# sbcs.net
KiCad netlist of a schematic drawn in Altium Designer
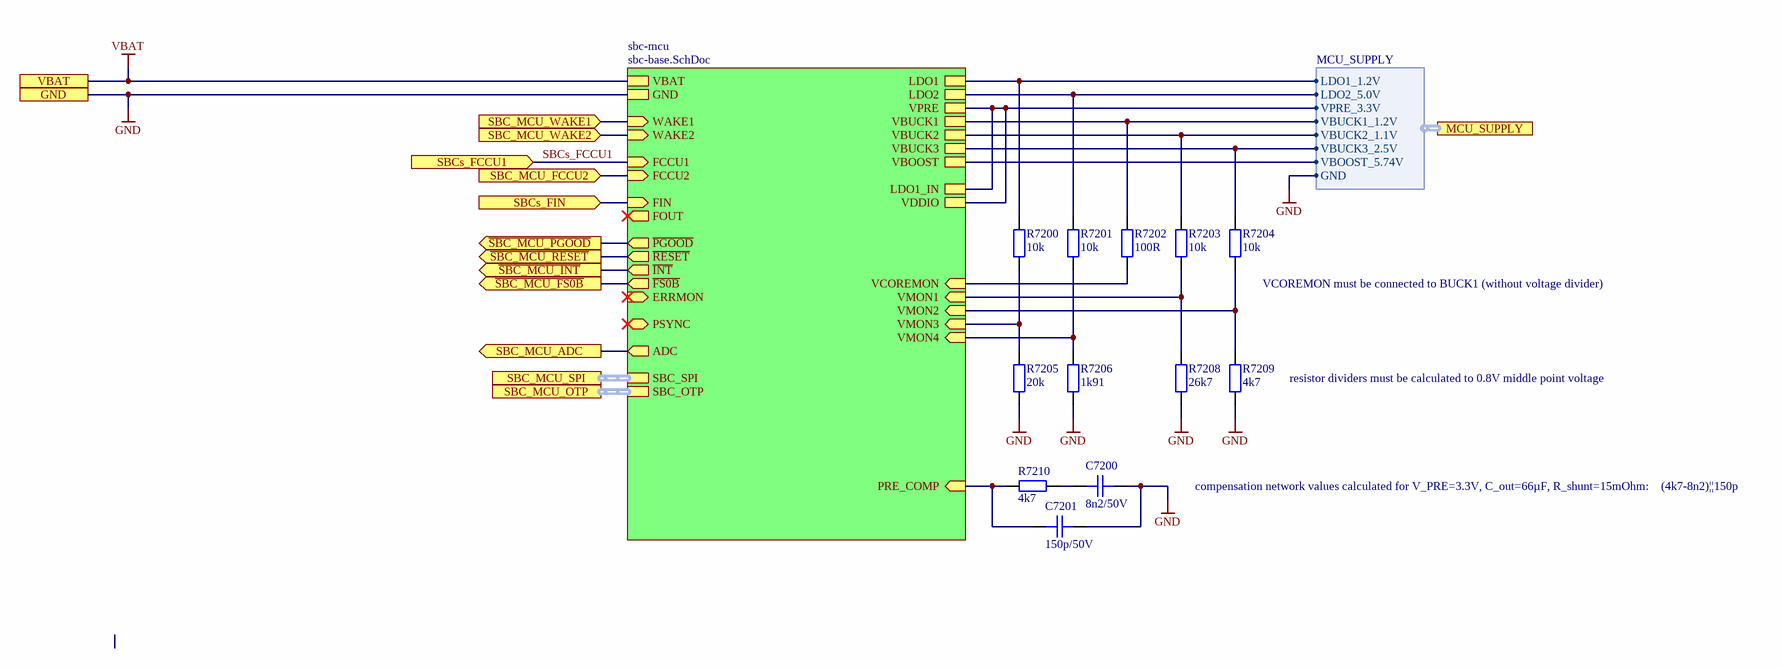
[diagram p0: sbcs.SchDoc]

(export (version "E")
  (design (tool "Eeschema 10.0.6"))
  (components
    (comp (ref "C7200")
      (value "8n2/50V")
      (footprint "CAPC1608X08N")
      (description "MLCC")
      (fields (field (name "PART NUMBER") "gen_C_ceramic_8n2_50V_C0G_0603"))
      (libsource (lib "OE750") (part "C"))
    )
    (comp (ref "C7201")
      (value "150p/50V")
      (footprint "CAPC1005X06N")
      (description "MLCC")
      (fields (field (name "PART NUMBER") "gen_C_ceramic_150p_50V_C0G_0402"))
      (libsource (lib "OE750") (part "C"))
    )
    (comp (ref "R7200")
      (value "10k")
      (footprint "RESC1005X04N")
      (description "SMD Resistor 10k 0402")
      (fields (field (name "PART NUMBER") "gen_R_10k_0402") (field (name "TOLERANCE") "1%"))
      (libsource (lib "OE750") (part "R"))
    )
    (comp (ref "R7201")
      (value "10k")
      (footprint "RESC1005X04N")
      (description "SMD Resistor 10k 0402")
      (fields (field (name "PART NUMBER") "gen_R_10k_0402") (field (name "TOLERANCE") "1%"))
      (libsource (lib "OE750") (part "R"))
    )
    (comp (ref "R7202")
      (value "100R")
      (footprint "RESC1005X04N")
      (description "SMD Resistor 100R 0402")
      (fields (field (name "PART NUMBER") "gen_R_100R_0402") (field (name "TOLERANCE") "1%"))
      (libsource (lib "OE750") (part "R"))
    )
    (comp (ref "R7203")
      (value "10k")
      (footprint "RESC1005X04N")
      (description "SMD Resistor 10k 0402")
      (fields (field (name "PART NUMBER") "gen_R_10k_0402") (field (name "TOLERANCE") "1%"))
      (libsource (lib "OE750") (part "R"))
    )
    (comp (ref "R7204")
      (value "10k")
      (footprint "RESC1005X04N")
      (description "SMD Resistor 10k 0402")
      (fields (field (name "PART NUMBER") "gen_R_10k_0402") (field (name "TOLERANCE") "1%"))
      (libsource (lib "OE750") (part "R"))
    )
    (comp (ref "R7205")
      (value "20k")
      (footprint "RESC1005X04N")
      (description "SMD Resistor 20k 0402")
      (fields (field (name "PART NUMBER") "gen_R_20k_0402") (field (name "TOLERANCE") "1%"))
      (libsource (lib "OE750") (part "R"))
    )
    (comp (ref "R7206")
      (value "1k91")
      (footprint "RESC1005X04N")
      (description "SMD Resistor 1k91 0402")
      (fields (field (name "PART NUMBER") "gen_R_1k91_0402") (field (name "TOLERANCE") "1%"))
      (libsource (lib "OE750") (part "R"))
    )
    (comp (ref "R7208")
      (value "26k7")
      (footprint "RESC1005X04N")
      (description "SMD Resistor 26k7 0402")
      (fields (field (name "PART NUMBER") "gen_R_26k7_0402") (field (name "TOLERANCE") "1%"))
      (libsource (lib "OE750") (part "R"))
    )
    (comp (ref "R7209")
      (value "4k7")
      (footprint "RESC1005X04N")
      (description "SMD Resistor 4k7 0402")
      (fields (field (name "PART NUMBER") "gen_R_4k7_0402") (field (name "TOLERANCE") "1%"))
      (libsource (lib "OE750") (part "R"))
    )
    (comp (ref "R7210")
      (value "4k7")
      (footprint "RESC1005X04N")
      (description "SMD Resistor 4k7 0402")
      (fields (field (name "PART NUMBER") "gen_R_4k7_0402") (field (name "TOLERANCE") "1%"))
      (libsource (lib "OE750") (part "R"))
    )
  )
  (nets
    (net (code "6") (name "/LDO1") (class "Default")
      (node (ref "R7200") (pin "2") (pinfunction "2_2") (pintype "passive"))
    )
    (net (code "8") (name "/LDO2") (class "Default")
      (node (ref "R7201") (pin "2") (pinfunction "2_2") (pintype "passive"))
    )
    (net (code "9") (name "/PRE_COMP") (class "Default")
      (node (ref "C7201") (pin "1") (pinfunction "1_1") (pintype "passive"))
      (node (ref "R7210") (pin "2") (pinfunction "2_2") (pintype "passive"))
    )
    (net (code "24") (name "/VBUCK1") (class "Default")
      (node (ref "R7202") (pin "2") (pinfunction "2_2") (pintype "passive"))
    )
    (net (code "25") (name "/VBUCK2") (class "Default")
      (node (ref "R7203") (pin "2") (pinfunction "2_2") (pintype "passive"))
    )
    (net (code "26") (name "/VBUCK3") (class "Default")
      (node (ref "R7204") (pin "2") (pinfunction "2_2") (pintype "passive"))
    )
    (net (code "27") (name "/VCOREMON") (class "Default")
      (node (ref "R7202") (pin "1") (pinfunction "1_1") (pintype "passive"))
    )
    (net (code "28") (name "/VMON1") (class "Default")
      (node (ref "R7203") (pin "1") (pinfunction "1_1") (pintype "passive"))
      (node (ref "R7208") (pin "2") (pinfunction "2_2") (pintype "passive"))
    )
    (net (code "29") (name "/VMON2") (class "Default")
      (node (ref "R7204") (pin "1") (pinfunction "1_1") (pintype "passive"))
      (node (ref "R7209") (pin "2") (pinfunction "2_2") (pintype "passive"))
    )
    (net (code "30") (name "/VMON3") (class "Default")
      (node (ref "R7200") (pin "1") (pinfunction "1_1") (pintype "passive"))
      (node (ref "R7205") (pin "2") (pinfunction "2_2") (pintype "passive"))
    )
    (net (code "31") (name "/VMON4") (class "Default")
      (node (ref "R7201") (pin "1") (pinfunction "1_1") (pintype "passive"))
      (node (ref "R7206") (pin "2") (pinfunction "2_2") (pintype "passive"))
    )
    (net (code "33") (name "GND") (class "Default")
      (node (ref "C7200") (pin "2") (pinfunction "2_2") (pintype "passive"))
      (node (ref "C7201") (pin "2") (pinfunction "2_2") (pintype "passive"))
      (node (ref "R7205") (pin "1") (pinfunction "1_1") (pintype "passive"))
      (node (ref "R7206") (pin "1") (pinfunction "1_1") (pintype "passive"))
      (node (ref "R7208") (pin "1") (pinfunction "1_1") (pintype "passive"))
      (node (ref "R7209") (pin "1") (pinfunction "1_1") (pintype "passive"))
    )
    (net (code "34") (name "Net-(C7200-Pad1)") (class "Default")
      (node (ref "C7200") (pin "1") (pinfunction "1_1") (pintype "passive"))
      (node (ref "R7210") (pin "1") (pinfunction "1_1") (pintype "passive"))
    )
  )
)
